# teensy_toslink_v1_1.net
KiCad netlist of a schematic drawn in EAGLE
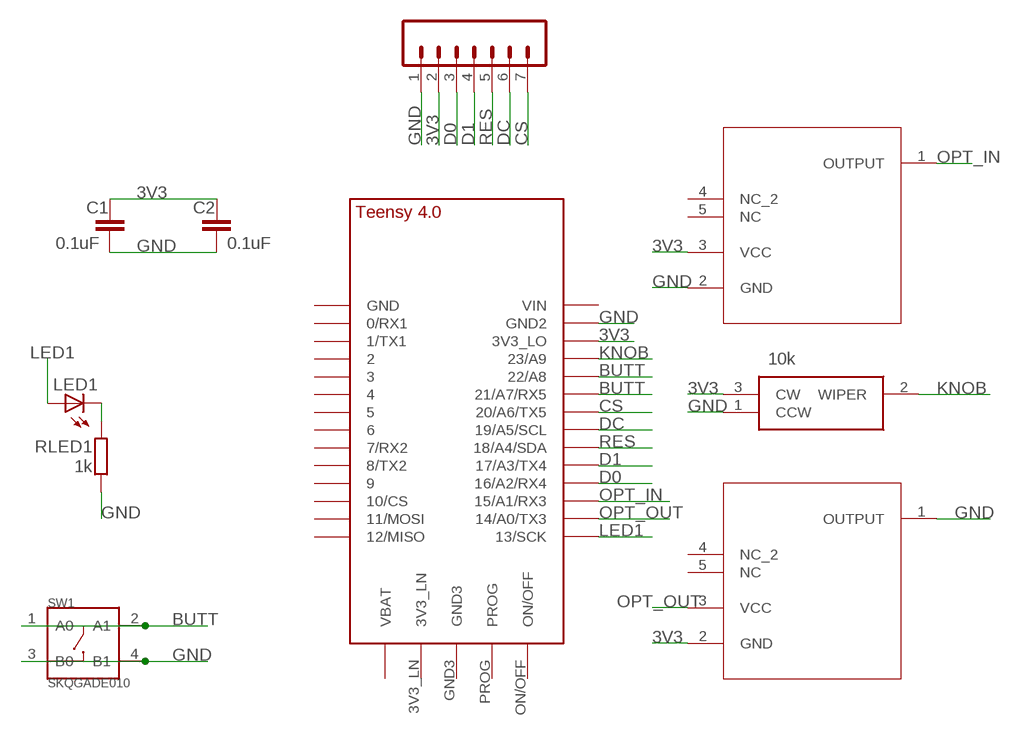
[diagram p0: schematic, sheet 1]

(export (version "E")
  (design (tool "Eeschema 10.0.6"))
  (components
    (comp (ref "C1")
      (value "0.1uF")
      (footprint "eagle-import:C0805")
      (libsource (lib "eagle-import") (part "C-EUC0805"))
    )
    (comp (ref "C2")
      (value "0.1uF")
      (footprint "eagle-import:C0805")
      (libsource (lib "eagle-import") (part "C-EUC0805"))
    )
    (comp (ref "CN1")
      (value "8p-2.54")
      (footprint "eagle-import:1X07")
      (libsource (lib "eagle-import") (part "CONN_07"))
    )
    (comp (ref "J1")
      (value "TORX141P(F)TORX141P(F)_TOS")
      (footprint "eagle-import:TORX141P(F)_TOS")
      (fields
        (field (name "MANUFACTURER_PART_NUMBER") "TORX141P(F)")
        (field (name "COPYRIGHT") "Copyright (C) 2023 Ultra Librarian. All rights reserved.")
      )
      (libsource (lib "eagle-import") (part "TORX141P(F)TORX141P(F)_TOS"))
    )
    (comp (ref "J2")
      (value "TORX141P(F)TORX141P(F)_TOS")
      (footprint "eagle-import:TORX141P(F)_TOS")
      (fields
        (field (name "MANUFACTURER_PART_NUMBER") "TORX141P(F)")
        (field (name "COPYRIGHT") "Copyright (C) 2023 Ultra Librarian. All rights reserved.")
      )
      (libsource (lib "eagle-import") (part "TORX141P(F)TORX141P(F)_TOS"))
    )
    (comp (ref "LED1")
      (value "0805")
      (footprint "eagle-import:CHIPLED_0805")
      (libsource (lib "eagle-import") (part "LEDCHIPLED_0805"))
    )
    (comp (ref "RLED1")
      (value "1k")
      (footprint "eagle-import:R0805")
      (libsource (lib "eagle-import") (part "R-EU_R0805"))
    )
    (comp (ref "SW1")
      (value "SKQGADE010")
      (footprint "eagle-import:SW4-SMD-5.2X5.2X1.5MM")
      (libsource (lib "eagle-import") (part "SMD-BUTTON(4P-5.2X5.2X1.5MM-SKQGADE010)-SKQGADE010"))
    )
    (comp (ref "U$1")
      (value "TEENSY_4.0")
      (footprint "eagle-import:TEENSY_4.0")
      (libsource (lib "eagle-import") (part "TEENSY_4.0"))
    )
    (comp (ref "VR1")
      (value "10k")
      (footprint "eagle-import:3386P1103TLF")
      (fields
        (field (name "MANUFACTURER_PART_NUMBER") "3386P-1-103")
        (field (name "MOUSER_PART_NUMBER") "652-3386P-1-103")
      )
      (libsource (lib "eagle-import") (part "3386P-1-103"))
    )
  )
  (nets
    (net (code "1") (name "/3V3") (class "Default")
      (node (ref "C1") (pin "1") (pinfunction "1_1") (pintype "passive"))
      (node (ref "C2") (pin "1") (pinfunction "1_1") (pintype "passive"))
      (node (ref "CN1") (pin "2") (pinfunction "2_2") (pintype "passive"))
      (node (ref "J1") (pin "3") (pinfunction "VCC_3") (pintype "power_in"))
      (node (ref "J2") (pin "2") (pinfunction "GND_2") (pintype "passive"))
      (node (ref "U$1") (pin "3V3_LO") (pinfunction "3V3_LO_3V3_LO") (pintype "bidirectional"))
      (node (ref "VR1") (pin "3") (pinfunction "CW_3") (pintype "bidirectional"))
    )
    (net (code "2") (name "/BUTT") (class "Default")
      (node (ref "SW1") (pin "1") (pinfunction "A0_1") (pintype "bidirectional"))
      (node (ref "SW1") (pin "2") (pinfunction "A1_2") (pintype "bidirectional"))
      (node (ref "U$1") (pin "21/A7") (pinfunction "21/A7/RX5_21/A7") (pintype "bidirectional"))
      (node (ref "U$1") (pin "22/A8") (pinfunction "22/A8_22/A8") (pintype "bidirectional"))
    )
    (net (code "3") (name "/CS") (class "Default")
      (node (ref "CN1") (pin "7") (pinfunction "7_7") (pintype "passive"))
      (node (ref "U$1") (pin "20/A6") (pinfunction "20/A6/TX5_20/A6") (pintype "bidirectional"))
    )
    (net (code "4") (name "/D0") (class "Default")
      (node (ref "CN1") (pin "3") (pinfunction "3_3") (pintype "passive"))
      (node (ref "U$1") (pin "16/A2") (pinfunction "16/A2/RX4_16/A2") (pintype "bidirectional"))
    )
    (net (code "5") (name "/D1") (class "Default")
      (node (ref "CN1") (pin "4") (pinfunction "4_4") (pintype "passive"))
      (node (ref "U$1") (pin "17/A3") (pinfunction "17/A3/TX4_17/A3") (pintype "bidirectional"))
    )
    (net (code "6") (name "/DC") (class "Default")
      (node (ref "CN1") (pin "6") (pinfunction "6_6") (pintype "passive"))
      (node (ref "U$1") (pin "19/A5/SCL") (pinfunction "19/A5/SCL_19/A5/SCL") (pintype "bidirectional"))
    )
    (net (code "7") (name "/GND") (class "Default")
      (node (ref "C1") (pin "2") (pinfunction "2_2") (pintype "passive"))
      (node (ref "C2") (pin "2") (pinfunction "2_2") (pintype "passive"))
      (node (ref "CN1") (pin "1") (pinfunction "1_1") (pintype "passive"))
      (node (ref "J1") (pin "2") (pinfunction "GND_2") (pintype "passive"))
      (node (ref "J2") (pin "1") (pinfunction "OUTPUT_1") (pintype "output"))
      (node (ref "RLED1") (pin "1") (pinfunction "1_1") (pintype "passive"))
      (node (ref "SW1") (pin "3") (pinfunction "B0_3") (pintype "bidirectional"))
      (node (ref "SW1") (pin "4") (pinfunction "B1_4") (pintype "bidirectional"))
      (node (ref "U$1") (pin "GND2") (pinfunction "GND2_GND2") (pintype "bidirectional"))
      (node (ref "VR1") (pin "1") (pinfunction "CCW_1") (pintype "bidirectional"))
    )
    (net (code "8") (name "/KNOB") (class "Default")
      (node (ref "U$1") (pin "23/A9") (pinfunction "23/A9_23/A9") (pintype "bidirectional"))
      (node (ref "VR1") (pin "2") (pinfunction "WIPER_2") (pintype "bidirectional"))
    )
    (net (code "9") (name "/LED1") (class "Default")
      (node (ref "LED1") (pin "A") (pinfunction "A_A") (pintype "passive"))
      (node (ref "U$1") (pin "13/SCK") (pinfunction "13/SCK_13/SCK") (pintype "bidirectional"))
    )
    (net (code "10") (name "/OPT_IN") (class "Default")
      (node (ref "J1") (pin "1") (pinfunction "OUTPUT_1") (pintype "output"))
      (node (ref "U$1") (pin "15/A1") (pinfunction "15/A1/RX3_15/A1") (pintype "bidirectional"))
    )
    (net (code "11") (name "/OPT_OUT") (class "Default")
      (node (ref "J2") (pin "3") (pinfunction "VCC_3") (pintype "power_in"))
      (node (ref "U$1") (pin "14/A0") (pinfunction "14/A0/TX3_14/A0") (pintype "bidirectional"))
    )
    (net (code "12") (name "/RES") (class "Default")
      (node (ref "CN1") (pin "5") (pinfunction "5_5") (pintype "passive"))
      (node (ref "U$1") (pin "18/A4/SDA") (pinfunction "18/A4/SDA_18/A4/SDA") (pintype "bidirectional"))
    )
    (net (code "13") (name "Net-(LED1-PadC)") (class "Default")
      (node (ref "LED1") (pin "C") (pinfunction "C_C") (pintype "passive"))
      (node (ref "RLED1") (pin "2") (pinfunction "2_2") (pintype "passive"))
    )
    (net (code "14") (name "unconnected-(J1-NC-Pad5)") (class "Default")
      (node (ref "J1") (pin "5") (pinfunction "NC_5") (pintype "no_connect"))
    )
    (net (code "15") (name "unconnected-(J1-NC_2-Pad4)") (class "Default")
      (node (ref "J1") (pin "4") (pinfunction "NC_2_4") (pintype "no_connect"))
    )
    (net (code "16") (name "unconnected-(J2-NC-Pad5)") (class "Default")
      (node (ref "J2") (pin "5") (pinfunction "NC_5") (pintype "no_connect"))
    )
    (net (code "17") (name "unconnected-(J2-NC_2-Pad4)") (class "Default")
      (node (ref "J2") (pin "4") (pinfunction "NC_2_4") (pintype "no_connect"))
    )
    (net (code "18") (name "unconnected-(U$1-0{slash}RX1-Pad0{slash}RX)") (class "Default")
      (node (ref "U$1") (pin "0/RX") (pinfunction "0/RX1_0/RX") (pintype "bidirectional"))
    )
    (net (code "19") (name "unconnected-(U$1-1{slash}TX1-Pad1{slash}TX)") (class "Default")
      (node (ref "U$1") (pin "1/TX") (pinfunction "1/TX1_1/TX") (pintype "bidirectional"))
    )
    (net (code "20") (name "unconnected-(U$1-3-Pad3{slash}CANTX)") (class "Default")
      (node (ref "U$1") (pin "3/CANTX") (pinfunction "3_3/CANTX") (pintype "bidirectional"))
    )
    (net (code "21") (name "unconnected-(U$1-4-Pad4{slash}CANRX)") (class "Default")
      (node (ref "U$1") (pin "4/CANRX") (pinfunction "4_4/CANRX") (pintype "bidirectional"))
    )
    (net (code "22") (name "unconnected-(U$1-7{slash}RX2-Pad7)") (class "Default")
      (node (ref "U$1") (pin "7") (pinfunction "7/RX2_7") (pintype "bidirectional"))
    )
    (net (code "23") (name "unconnected-(U$1-8{slash}TX2-Pad8)") (class "Default")
      (node (ref "U$1") (pin "8") (pinfunction "8/TX2_8") (pintype "bidirectional"))
    )
    (net (code "24") (name "unconnected-(U$1-9-Pad9{slash}CS)") (class "Default")
      (node (ref "U$1") (pin "9/CS") (pinfunction "9_9/CS") (pintype "bidirectional"))
    )
    (net (code "25") (name "unconnected-(U$1-Pad2)") (class "Default")
      (node (ref "U$1") (pin "2") (pinfunction "2_2") (pintype "bidirectional"))
    )
    (net (code "26") (name "unconnected-(U$1-Pad3V3_LN)") (class "Default")
      (node (ref "U$1") (pin "3V3_LN") (pinfunction "3V3_LN_3V3_LN") (pintype "bidirectional"))
    )
    (net (code "27") (name "unconnected-(U$1-Pad5)") (class "Default")
      (node (ref "U$1") (pin "5") (pinfunction "5_5") (pintype "bidirectional"))
    )
    (net (code "28") (name "unconnected-(U$1-Pad6)") (class "Default")
      (node (ref "U$1") (pin "6") (pinfunction "6_6") (pintype "bidirectional"))
    )
    (net (code "29") (name "unconnected-(U$1-Pad10{slash}CS)") (class "Default")
      (node (ref "U$1") (pin "10/CS") (pinfunction "10/CS_10/CS") (pintype "bidirectional"))
    )
    (net (code "30") (name "unconnected-(U$1-Pad11{slash}MOSI)") (class "Default")
      (node (ref "U$1") (pin "11/MOSI") (pinfunction "11/MOSI_11/MOSI") (pintype "bidirectional"))
    )
    (net (code "31") (name "unconnected-(U$1-Pad12{slash}MISO)") (class "Default")
      (node (ref "U$1") (pin "12/MISO") (pinfunction "12/MISO_12/MISO") (pintype "bidirectional"))
    )
    (net (code "32") (name "unconnected-(U$1-PadGND)") (class "Default")
      (node (ref "U$1") (pin "GND") (pinfunction "GND_GND") (pintype "bidirectional"))
    )
    (net (code "33") (name "unconnected-(U$1-PadGND3)") (class "Default")
      (node (ref "U$1") (pin "GND3") (pinfunction "GND3_GND3") (pintype "bidirectional"))
    )
    (net (code "34") (name "unconnected-(U$1-PadON{slash}OFF)") (class "Default")
      (node (ref "U$1") (pin "ON/OFF") (pinfunction "ON/OFF_ON/OFF") (pintype "bidirectional"))
    )
    (net (code "35") (name "unconnected-(U$1-PadPROG)") (class "Default")
      (node (ref "U$1") (pin "PROG") (pinfunction "PROG_PROG") (pintype "bidirectional"))
    )
    (net (code "36") (name "unconnected-(U$1-PadVIN)") (class "Default")
      (node (ref "U$1") (pin "VIN") (pinfunction "VIN_VIN") (pintype "bidirectional"))
    )
    (net (code "37") (name "unconnected-(U$1-VBAT-PadVBAT\\)") (class "Default")
      (node (ref "U$1") (pin "VBAT\\") (pinfunction "VBAT_VBAT\\") (pintype "bidirectional"))
    )
  )
)
